# MAX30102.net
KiCad netlist of a schematic drawn in Altium Designer
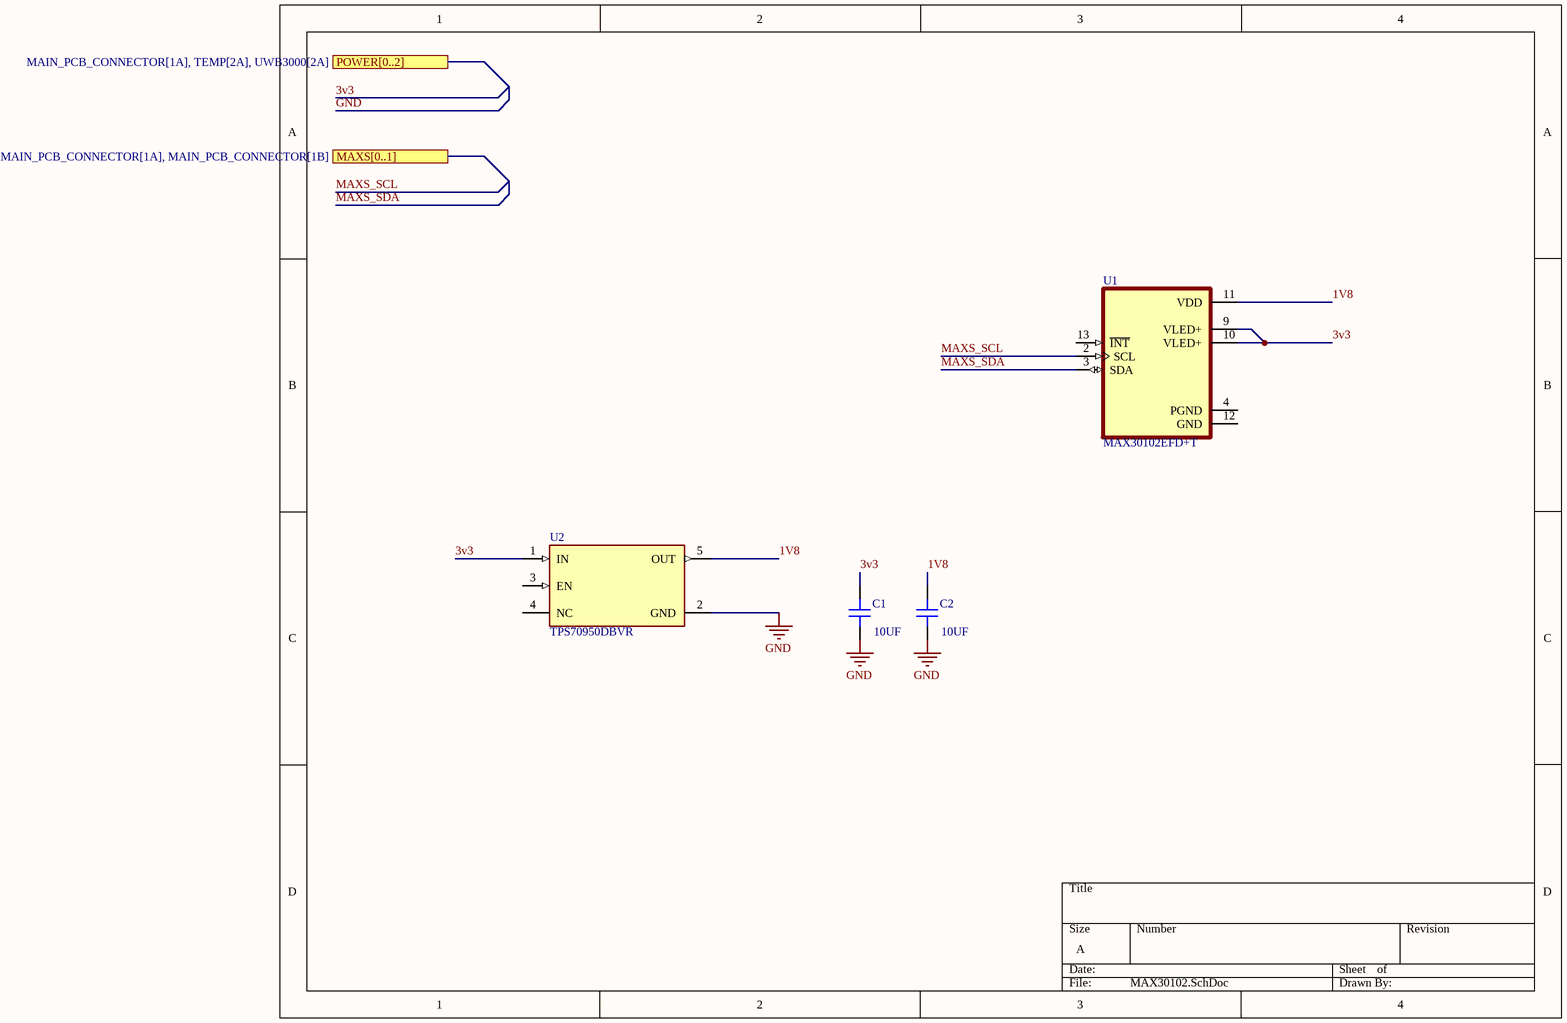
[diagram p0: MAX30102.SchDoc]

(export (version "E")
  (design (tool "Eeschema 10.0.6"))
  (components
    (comp (ref "C1")
      (value "10UF")
      (footprint "CAP 0402_1005")
      (description "CAP CER 10UF 6.3V X5R 0402")
      (fields (field (name "JLCPCB PART #") "C15525") (field (name "MFR.PART #") "CL05A106MQ5NUNC"))
      (libsource (lib "Celestial Altium Library - altium_library") (part "Capacitor"))
    )
    (comp (ref "C2")
      (value "10UF")
      (footprint "CAP 0402_1005")
      (description "CAP CER 10UF 6.3V X5R 0402")
      (fields (field (name "JLCPCB PART #") "C15525") (field (name "MFR.PART #") "CL05A106MQ5NUNC"))
      (libsource (lib "Celestial Altium Library - altium_library") (part "Capacitor"))
    )
    (comp (ref "U1")
      (value "MAX30102EFD+T")
      (footprint "XDCR_MAX30101EFD+")
      (description "Pulse Oximeter and Heart Rate Sensor Digital Output")
      (fields
        (field (name "JLCPCB PART #") "C6454833")
        (field (name "MANUFACTURER") "Analog Devices Inc./Maxim Integrated")
      )
      (libsource (lib "MAX30102EFD_T") (part "MAX30102EFD+T"))
    )
    (comp (ref "U2")
      (value "TPS70950DBVR")
      (footprint "SOT95P280X145-5N")
      (fields (field (name "JLCPCB PART #") "C96028") (field (name "MANUFACTURER") "Texas Instruments"))
      (libsource (lib "TPS70950DBVR") (part "TPS70950DBVR"))
    )
  )
  (nets
    (net (code "6") (name "/1V8") (class "Default")
      (node (ref "C2") (pin "2") (pinfunction "2_2") (pintype "passive"))
      (node (ref "U1") (pin "11") (pinfunction "VDD_11") (pintype "power_in"))
      (node (ref "U2") (pin "5") (pinfunction "OUT_5") (pintype "output"))
    )
    (net (code "7") (name "/3v3") (class "Default")
      (node (ref "C1") (pin "2") (pinfunction "2_2") (pintype "passive"))
      (node (ref "U1") (pin "10") (pinfunction "VLED+_10") (pintype "power_in"))
      (node (ref "U1") (pin "9") (pinfunction "VLED+_9") (pintype "power_in"))
      (node (ref "U2") (pin "1") (pinfunction "IN_1") (pintype "input"))
    )
    (net (code "9") (name "/MAXS_SCL") (class "Default")
      (node (ref "U1") (pin "2") (pinfunction "SCL_2") (pintype "input"))
    )
    (net (code "10") (name "/MAXS_SDA") (class "Default")
      (node (ref "U1") (pin "3") (pinfunction "SDA_3") (pintype "bidirectional"))
    )
    (net (code "12") (name "GND") (class "Default")
      (node (ref "C1") (pin "1") (pinfunction "1_1") (pintype "passive"))
      (node (ref "C2") (pin "1") (pinfunction "1_1") (pintype "passive"))
      (node (ref "U2") (pin "2") (pinfunction "GND_2") (pintype "power_in"))
    )
    (net (code "13") (name "unconnected-(U1-GND-Pad12)") (class "Default")
      (node (ref "U1") (pin "12") (pinfunction "GND_12") (pintype "power_in"))
    )
    (net (code "14") (name "unconnected-(U1-PGND-Pad4)") (class "Default")
      (node (ref "U1") (pin "4") (pinfunction "PGND_4") (pintype "power_in"))
    )
    (net (code "15") (name "unconnected-(U1-~{INT}-Pad13)") (class "Default")
      (node (ref "U1") (pin "13") (pinfunction "~{INT}_13") (pintype "input"))
    )
    (net (code "16") (name "unconnected-(U2-EN-Pad3)") (class "Default")
      (node (ref "U2") (pin "3") (pinfunction "EN_3") (pintype "input"))
    )
    (net (code "17") (name "unconnected-(U2-NC-Pad4)") (class "Default")
      (node (ref "U2") (pin "4") (pinfunction "NC_4") (pintype "passive"))
    )
  )
)
